# Peripheral.net
KiCad netlist of a schematic drawn in Altium Designer
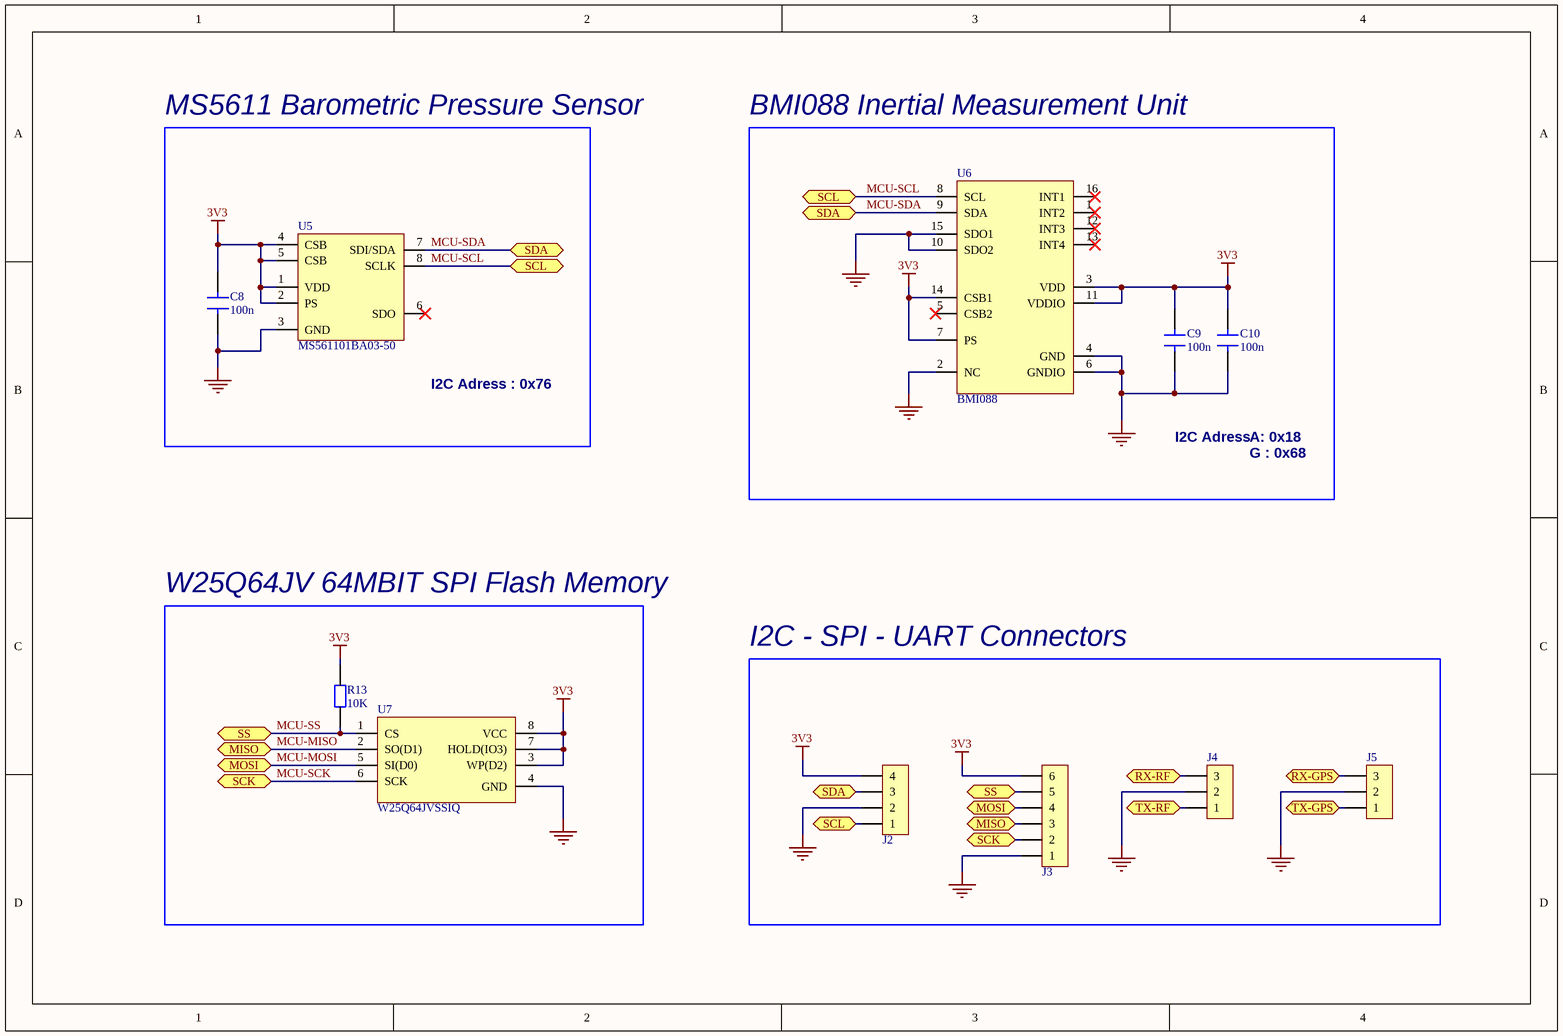
[diagram p0: Peripheral.SchDoc]

(export (version "E")
  (design (tool "Eeschema 10.0.6"))
  (components
    (comp (ref "C8")
      (value "100n")
      (footprint "CAP 0603")
      (description "Capacitor SMD 0603 50V")
      (libsource (lib "Schlib") (part "CAP 0603 50V"))
    )
    (comp (ref "C9")
      (value "100n")
      (footprint "CAP 0603")
      (description "Capacitor SMD 0603 50V")
      (libsource (lib "Schlib") (part "CAP 0603 50V"))
    )
    (comp (ref "C10")
      (value "100n")
      (footprint "CAP 0603")
      (description "Capacitor SMD 0603 50V")
      (libsource (lib "Schlib") (part "CAP 0603 50V"))
    )
    (comp (ref "J2")
      (value "1x4 HEADER MALE")
      (footprint "1X4 HEADER MALE")
      (libsource (lib "Schlib") (part "1x4 HEADER MALE"))
    )
    (comp (ref "J3")
      (value "1x6 HEADER MALE")
      (footprint "1X6 HEADER MALE")
      (libsource (lib "Schlib") (part "1x6 HEADER MALE"))
    )
    (comp (ref "J4")
      (value "JST B3B-XH-A")
      (footprint "JST_B3B-XH-A")
      (description "Connector Header, XH Series, 3 Position, 2.50mm, Through Hole, Press-Fit, Solder, Natural")
      (fields
        (field (name "MANUFACTURER") "JST")
        (field (name "MANUFACTURER PART NUMBER") "B3B-XH-A(LF)(SN)")
      )
      (libsource (lib "Schlib") (part "JST B3B-XH-A"))
    )
    (comp (ref "J5")
      (value "JST B3B-XH-A")
      (footprint "JST_B3B-XH-A")
      (description "Connector Header, XH Series, 3 Position, 2.50mm, Through Hole, Press-Fit, Solder, Natural")
      (fields
        (field (name "MANUFACTURER") "JST")
        (field (name "MANUFACTURER PART NUMBER") "B3B-XH-A(LF)(SN)")
      )
      (libsource (lib "Schlib") (part "JST B3B-XH-A"))
    )
    (comp (ref "R13")
      (value "10K")
      (footprint "RES 0603")
      (description "Resistor SMD 0603")
      (libsource (lib "Schlib") (part "RES 0603"))
    )
    (comp (ref "U5")
      (value "MS561101BA03-50")
      (footprint "MS5611-01BA3")
      (description "Pressure Sensor 1.44V to 3.6V 0.01bar to 1.2bar Absolute 8-Pin QFN T/R")
      (fields (field (name "MANUFACTURER") "TE Connectivity"))
      (libsource (lib "Schlib") (part "MS561101BA03-50"))
    )
    (comp (ref "U6")
      (value "BMI088")
      (footprint "BMI088")
      (description "BMI088 Series 3.6 V 6 Axis Digital Output Accelerometer Motion Sensor - LGA-16")
      (fields (field (name "MANUFACTURER") "Bosch Tools"))
      (libsource (lib "Schlib") (part "BMI088"))
    )
    (comp (ref "U7")
      (value "W25Q64JVSSIQ")
      (footprint "W25Q64JVSSIQ")
      (description "IC FLASH 64MBIT 104MHZ 8SOIC")
      (fields (field (name "MANUFACTURER") "Winbond"))
      (libsource (lib "Schlib") (part "W25Q64JVSSIQ"))
    )
  )
  (nets
    (net (code "1") (name "/MCU-MISO") (class "Default")
      (node (ref "J3") (pin "3") (pinfunction "3_3") (pintype "passive"))
      (node (ref "U7") (pin "2") (pinfunction "SO(D1)_2") (pintype "passive"))
    )
    (net (code "2") (name "/MCU-MOSI") (class "Default")
      (node (ref "J3") (pin "4") (pinfunction "4_4") (pintype "passive"))
      (node (ref "U7") (pin "5") (pinfunction "SI(D0)_5") (pintype "passive"))
    )
    (net (code "3") (name "/MCU-SCK") (class "Default")
      (node (ref "J3") (pin "2") (pinfunction "2_2") (pintype "passive"))
      (node (ref "U7") (pin "6") (pinfunction "SCK_6") (pintype "passive"))
    )
    (net (code "4") (name "/MCU-SCL") (class "Default")
      (node (ref "J2") (pin "1") (pinfunction "1_1") (pintype "passive"))
      (node (ref "U5") (pin "8") (pinfunction "SCLK_8") (pintype "passive"))
      (node (ref "U6") (pin "8") (pinfunction "SCL_8") (pintype "passive"))
    )
    (net (code "5") (name "/MCU-SDA") (class "Default")
      (node (ref "J2") (pin "3") (pinfunction "3_3") (pintype "passive"))
      (node (ref "U5") (pin "7") (pinfunction "SDI/SDA_7") (pintype "passive"))
      (node (ref "U6") (pin "9") (pinfunction "SDA_9") (pintype "passive"))
    )
    (net (code "6") (name "/MCU-SS") (class "Default")
      (node (ref "J3") (pin "5") (pinfunction "5_5") (pintype "passive"))
      (node (ref "R13") (pin "1") (pinfunction "1_1") (pintype "passive"))
      (node (ref "U7") (pin "1") (pinfunction "CS_1") (pintype "passive"))
    )
    (net (code "7") (name "/RX-GPS") (class "Default")
      (node (ref "J5") (pin "3") (pinfunction "3_3") (pintype "passive"))
    )
    (net (code "8") (name "/RX-RF") (class "Default")
      (node (ref "J4") (pin "3") (pinfunction "3_3") (pintype "passive"))
    )
    (net (code "9") (name "/TX-GPS") (class "Default")
      (node (ref "J5") (pin "1") (pinfunction "1_1") (pintype "passive"))
    )
    (net (code "10") (name "/TX-RF") (class "Default")
      (node (ref "J4") (pin "1") (pinfunction "1_1") (pintype "passive"))
    )
    (net (code "11") (name "3V3") (class "Default")
      (node (ref "C10") (pin "2") (pinfunction "2_2") (pintype "passive"))
      (node (ref "C8") (pin "2") (pinfunction "2_2") (pintype "passive"))
      (node (ref "C9") (pin "2") (pinfunction "2_2") (pintype "passive"))
      (node (ref "J2") (pin "4") (pinfunction "4_4") (pintype "passive"))
      (node (ref "J3") (pin "6") (pinfunction "6_6") (pintype "passive"))
      (node (ref "R13") (pin "2") (pinfunction "2_2") (pintype "passive"))
      (node (ref "U5") (pin "1") (pinfunction "VDD_1") (pintype "passive"))
      (node (ref "U5") (pin "2") (pinfunction "PS_2") (pintype "passive"))
      (node (ref "U5") (pin "4") (pinfunction "CSB_4") (pintype "passive"))
      (node (ref "U5") (pin "5") (pinfunction "CSB_5") (pintype "passive"))
      (node (ref "U6") (pin "11") (pinfunction "VDDIO_11") (pintype "passive"))
      (node (ref "U6") (pin "14") (pinfunction "CSB1_14") (pintype "passive"))
      (node (ref "U6") (pin "3") (pinfunction "VDD_3") (pintype "passive"))
      (node (ref "U6") (pin "7") (pinfunction "PS_7") (pintype "passive"))
      (node (ref "U7") (pin "3") (pinfunction "WP(D2)_3") (pintype "passive"))
      (node (ref "U7") (pin "7") (pinfunction "HOLD(IO3)_7") (pintype "passive"))
      (node (ref "U7") (pin "8") (pinfunction "VCC_8") (pintype "passive"))
    )
    (net (code "12") (name "GND") (class "Default")
      (node (ref "C10") (pin "1") (pinfunction "1_1") (pintype "passive"))
      (node (ref "C8") (pin "1") (pinfunction "1_1") (pintype "passive"))
      (node (ref "C9") (pin "1") (pinfunction "1_1") (pintype "passive"))
      (node (ref "J2") (pin "2") (pinfunction "2_2") (pintype "passive"))
      (node (ref "J3") (pin "1") (pinfunction "1_1") (pintype "passive"))
      (node (ref "J4") (pin "2") (pinfunction "2_2") (pintype "passive"))
      (node (ref "J5") (pin "2") (pinfunction "2_2") (pintype "passive"))
      (node (ref "U5") (pin "3") (pinfunction "GND_3") (pintype "passive"))
      (node (ref "U6") (pin "10") (pinfunction "SDO2_10") (pintype "passive"))
      (node (ref "U6") (pin "15") (pinfunction "SDO1_15") (pintype "passive"))
      (node (ref "U6") (pin "2") (pinfunction "NC_2") (pintype "passive"))
      (node (ref "U6") (pin "4") (pinfunction "GND_4") (pintype "passive"))
      (node (ref "U6") (pin "6") (pinfunction "GNDIO_6") (pintype "passive"))
      (node (ref "U7") (pin "4") (pinfunction "GND_4") (pintype "passive"))
    )
    (net (code "13") (name "unconnected-(U5-SDO-Pad6)") (class "Default")
      (node (ref "U5") (pin "6") (pinfunction "SDO_6") (pintype "passive+no_connect"))
    )
    (net (code "14") (name "unconnected-(U6-CSB2-Pad5)") (class "Default")
      (node (ref "U6") (pin "5") (pinfunction "CSB2_5") (pintype "passive+no_connect"))
    )
    (net (code "15") (name "unconnected-(U6-INT1-Pad16)") (class "Default")
      (node (ref "U6") (pin "16") (pinfunction "INT1_16") (pintype "passive+no_connect"))
    )
    (net (code "16") (name "unconnected-(U6-INT2-Pad1)") (class "Default")
      (node (ref "U6") (pin "1") (pinfunction "INT2_1") (pintype "passive+no_connect"))
    )
    (net (code "17") (name "unconnected-(U6-INT3-Pad12)") (class "Default")
      (node (ref "U6") (pin "12") (pinfunction "INT3_12") (pintype "passive+no_connect"))
    )
    (net (code "18") (name "unconnected-(U6-INT4-Pad13)") (class "Default")
      (node (ref "U6") (pin "13") (pinfunction "INT4_13") (pintype "passive+no_connect"))
    )
  )
)
